# lt1236LS8_reference_module.net
KiCad netlist of a schematic drawn in EAGLE
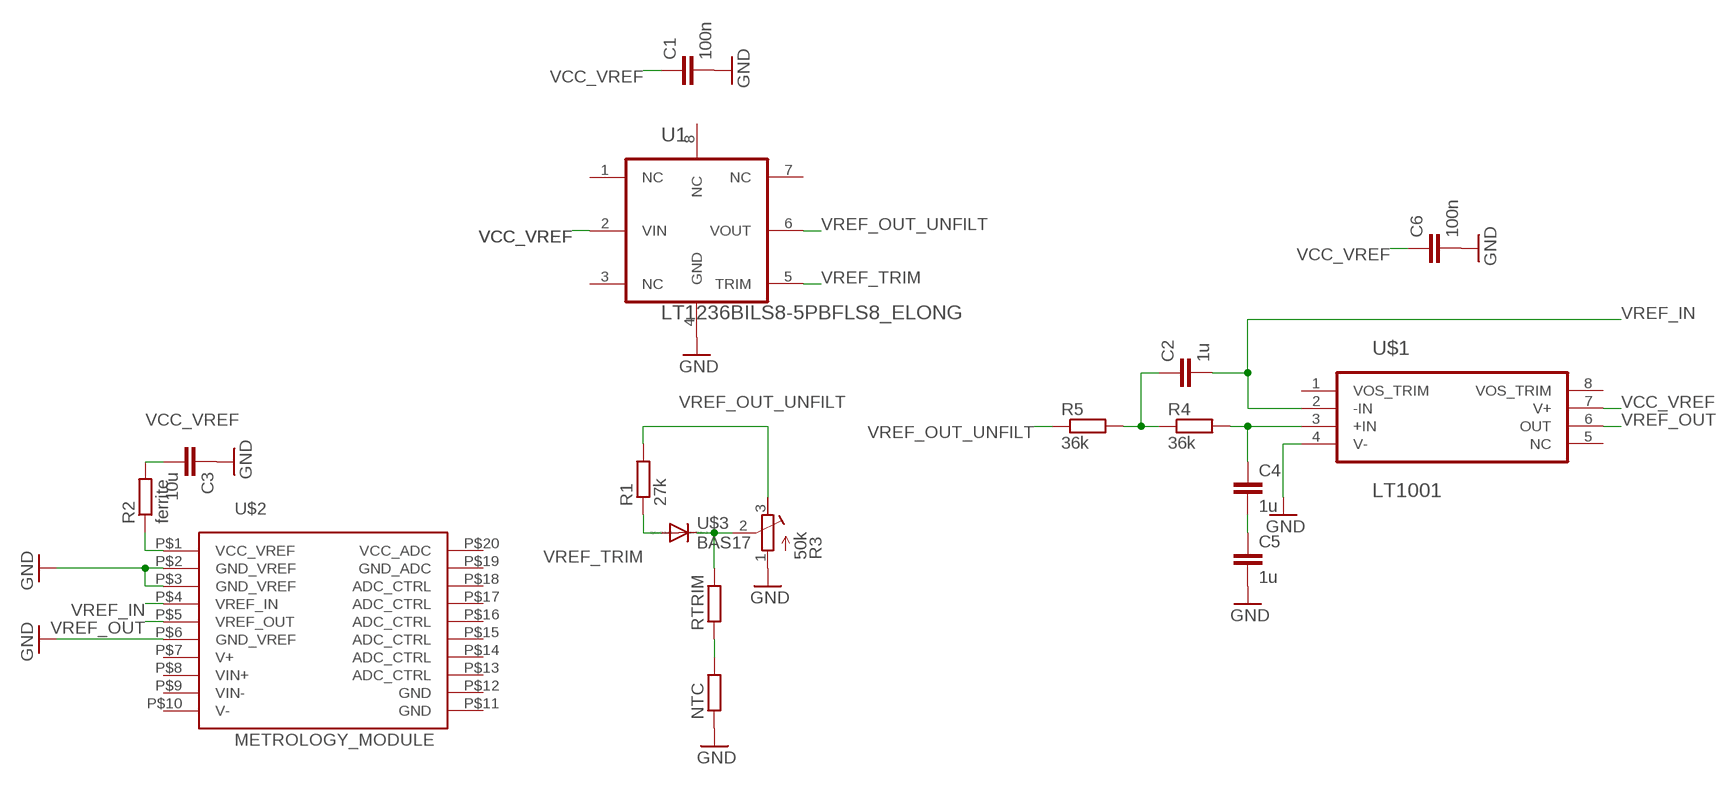
[diagram p0: schematic, sheet 1]

(export (version "E")
  (design (tool "Eeschema 10.0.6"))
  (components
    (comp (ref "C1")
      (value "100n")
      (footprint "eagle-import:C0603")
      (libsource (lib "eagle-import") (part "C-EUC0603"))
    )
    (comp (ref "C2")
      (value "1u")
      (footprint "eagle-import:C025-060X050")
      (libsource (lib "eagle-import") (part "C-EU025-060X050"))
    )
    (comp (ref "C3")
      (value "10u")
      (footprint "eagle-import:C0805")
      (libsource (lib "eagle-import") (part "C-EUC0805"))
    )
    (comp (ref "C4")
      (value "1u")
      (footprint "eagle-import:C025-060X050")
      (libsource (lib "eagle-import") (part "C-EU025-060X050"))
    )
    (comp (ref "C5")
      (value "1u")
      (footprint "eagle-import:C025-060X050")
      (libsource (lib "eagle-import") (part "C-EU025-060X050"))
    )
    (comp (ref "C6")
      (value "100n")
      (footprint "eagle-import:C0603")
      (libsource (lib "eagle-import") (part "C-EUC0603"))
    )
    (comp (ref "NTC")
      (value "R-EU_R0805")
      (footprint "eagle-import:R0805")
      (libsource (lib "eagle-import") (part "R-EU_R0805"))
    )
    (comp (ref "R1")
      (value "27k")
      (footprint "eagle-import:R0805")
      (libsource (lib "eagle-import") (part "R-EU_R0805"))
    )
    (comp (ref "R2")
      (value "ferrite")
      (footprint "eagle-import:R0805")
      (libsource (lib "eagle-import") (part "R-EU_R0805"))
    )
    (comp (ref "R3")
      (value "50k")
      (footprint "eagle-import:RTRIM3224W")
      (libsource (lib "eagle-import") (part "R-TRIMM3224W"))
    )
    (comp (ref "R4")
      (value "36k")
      (footprint "eagle-import:R0805")
      (libsource (lib "eagle-import") (part "R-EU_R0805"))
    )
    (comp (ref "R5")
      (value "36k")
      (footprint "eagle-import:R0805")
      (libsource (lib "eagle-import") (part "R-EU_R0805"))
    )
    (comp (ref "RTRIM")
      (value "R-EU_R0805")
      (footprint "eagle-import:R0805")
      (libsource (lib "eagle-import") (part "R-EU_R0805"))
    )
    (comp (ref "U$1")
      (value "LT1001")
      (footprint "eagle-import:N8-PDIP8")
      (libsource (lib "eagle-import") (part "LT1001"))
    )
    (comp (ref "U$2")
      (value "METROLOGY_MODULE")
      (footprint "eagle-import:METROLOGY_MODULE")
      (libsource (lib "eagle-import") (part "METROLOGY_MODULE"))
    )
    (comp (ref "U$3")
      (value "BAS17")
      (footprint "eagle-import:SOT23_HAND")
      (libsource (lib "eagle-import") (part "BAS17"))
    )
    (comp (ref "U1")
      (value "LT1236BILS8-5PBFLS8_ELONG")
      (footprint "eagle-import:LS8_ELONG")
      (libsource (lib "eagle-import") (part "LT1236BILS8-5PBFLS8_ELONG"))
    )
  )
  (nets
    (net (code "1") (name "/VCC_VREF") (class "Default")
      (node (ref "C1") (pin "1") (pinfunction "1_1") (pintype "passive"))
      (node (ref "C3") (pin "2") (pinfunction "2_2") (pintype "passive"))
      (node (ref "C6") (pin "1") (pinfunction "1_1") (pintype "passive"))
      (node (ref "R2") (pin "2") (pinfunction "2_2") (pintype "passive"))
      (node (ref "U$1") (pin "7") (pinfunction "V+_7") (pintype "bidirectional"))
      (node (ref "U1") (pin "2") (pinfunction "VIN_2") (pintype "input"))
    )
    (net (code "2") (name "/VREF_IN") (class "Default")
      (node (ref "C2") (pin "2") (pinfunction "2_2") (pintype "passive"))
      (node (ref "U$1") (pin "2") (pinfunction "-IN_2") (pintype "bidirectional"))
      (node (ref "U$2") (pin "P$4") (pinfunction "VREF_IN_P$4") (pintype "bidirectional"))
    )
    (net (code "3") (name "/VREF_OUT") (class "Default")
      (node (ref "U$1") (pin "6") (pinfunction "OUT_6") (pintype "bidirectional"))
      (node (ref "U$2") (pin "P$5") (pinfunction "VREF_OUT_P$5") (pintype "bidirectional"))
    )
    (net (code "4") (name "/VREF_OUT_UNFILT") (class "Default")
      (node (ref "R1") (pin "2") (pinfunction "2_2") (pintype "passive"))
      (node (ref "R3") (pin "3") (pinfunction "A_3") (pintype "passive"))
      (node (ref "R5") (pin "1") (pinfunction "1_1") (pintype "passive"))
      (node (ref "U1") (pin "6") (pinfunction "VOUT_6") (pintype "output"))
    )
    (net (code "5") (name "/VREF_TRIM") (class "Default")
      (node (ref "R1") (pin "1") (pinfunction "1_1") (pintype "passive"))
      (node (ref "U$3") (pin "1") (pinfunction "A_1") (pintype "passive"))
      (node (ref "U1") (pin "5") (pinfunction "TRIM_5") (pintype "input"))
    )
    (net (code "6") (name "GND") (class "Default")
      (node (ref "C1") (pin "2") (pinfunction "2_2") (pintype "passive"))
      (node (ref "C3") (pin "1") (pinfunction "1_1") (pintype "passive"))
      (node (ref "C5") (pin "2") (pinfunction "2_2") (pintype "passive"))
      (node (ref "C6") (pin "2") (pinfunction "2_2") (pintype "passive"))
      (node (ref "NTC") (pin "1") (pinfunction "1_1") (pintype "passive"))
      (node (ref "R3") (pin "1") (pinfunction "E_1") (pintype "passive"))
      (node (ref "U$1") (pin "4") (pinfunction "V-_4") (pintype "bidirectional"))
      (node (ref "U$2") (pin "P$2") (pinfunction "GND_VREF_P$2") (pintype "bidirectional"))
      (node (ref "U$2") (pin "P$3") (pinfunction "GND_VREF_P$3") (pintype "bidirectional"))
      (node (ref "U$2") (pin "P$6") (pinfunction "GND_VREF_P$6") (pintype "bidirectional"))
      (node (ref "U1") (pin "4") (pinfunction "GND_4") (pintype "passive"))
    )
    (net (code "7") (name "Net-(C2-Pad1)") (class "Default")
      (node (ref "C2") (pin "1") (pinfunction "1_1") (pintype "passive"))
      (node (ref "R4") (pin "1") (pinfunction "1_1") (pintype "passive"))
      (node (ref "R5") (pin "2") (pinfunction "2_2") (pintype "passive"))
    )
    (net (code "8") (name "Net-(C4-Pad2)") (class "Default")
      (node (ref "C4") (pin "2") (pinfunction "2_2") (pintype "passive"))
      (node (ref "C5") (pin "1") (pinfunction "1_1") (pintype "passive"))
    )
    (net (code "9") (name "Net-(NTC-Pad2)") (class "Default")
      (node (ref "NTC") (pin "2") (pinfunction "2_2") (pintype "passive"))
      (node (ref "RTRIM") (pin "1") (pinfunction "1_1") (pintype "passive"))
    )
    (net (code "10") (name "Net-(R3-S)") (class "Default")
      (node (ref "R3") (pin "2") (pinfunction "S_2") (pintype "passive"))
      (node (ref "RTRIM") (pin "2") (pinfunction "2_2") (pintype "passive"))
      (node (ref "U$3") (pin "3") (pinfunction "C_3") (pintype "passive"))
    )
    (net (code "11") (name "Net-(U$1-+IN)") (class "Default")
      (node (ref "C4") (pin "1") (pinfunction "1_1") (pintype "passive"))
      (node (ref "R4") (pin "2") (pinfunction "2_2") (pintype "passive"))
      (node (ref "U$1") (pin "3") (pinfunction "+IN_3") (pintype "bidirectional"))
    )
    (net (code "12") (name "Net-(U$2-VCC_VREF)") (class "Default")
      (node (ref "R2") (pin "1") (pinfunction "1_1") (pintype "passive"))
      (node (ref "U$2") (pin "P$1") (pinfunction "VCC_VREF_P$1") (pintype "bidirectional"))
    )
    (net (code "13") (name "unconnected-(U$1-NC-Pad5)") (class "Default")
      (node (ref "U$1") (pin "5") (pinfunction "NC_5") (pintype "bidirectional"))
    )
    (net (code "14") (name "unconnected-(U$1-VOS_TRIM-Pad1)") (class "Default")
      (node (ref "U$1") (pin "1") (pinfunction "VOS_TRIM_1") (pintype "bidirectional"))
    )
    (net (code "15") (name "unconnected-(U$1-VOS_TRIM-Pad8)") (class "Default")
      (node (ref "U$1") (pin "8") (pinfunction "VOS_TRIM_8") (pintype "bidirectional"))
    )
    (net (code "16") (name "unconnected-(U$2-ADC_CTRL-PadP$13)") (class "Default")
      (node (ref "U$2") (pin "P$13") (pinfunction "ADC_CTRL_P$13") (pintype "bidirectional"))
    )
    (net (code "17") (name "unconnected-(U$2-ADC_CTRL-PadP$14)") (class "Default")
      (node (ref "U$2") (pin "P$14") (pinfunction "ADC_CTRL_P$14") (pintype "bidirectional"))
    )
    (net (code "18") (name "unconnected-(U$2-ADC_CTRL-PadP$15)") (class "Default")
      (node (ref "U$2") (pin "P$15") (pinfunction "ADC_CTRL_P$15") (pintype "bidirectional"))
    )
    (net (code "19") (name "unconnected-(U$2-ADC_CTRL-PadP$16)") (class "Default")
      (node (ref "U$2") (pin "P$16") (pinfunction "ADC_CTRL_P$16") (pintype "bidirectional"))
    )
    (net (code "20") (name "unconnected-(U$2-ADC_CTRL-PadP$17)") (class "Default")
      (node (ref "U$2") (pin "P$17") (pinfunction "ADC_CTRL_P$17") (pintype "bidirectional"))
    )
    (net (code "21") (name "unconnected-(U$2-ADC_CTRL-PadP$18)") (class "Default")
      (node (ref "U$2") (pin "P$18") (pinfunction "ADC_CTRL_P$18") (pintype "bidirectional"))
    )
    (net (code "22") (name "unconnected-(U$2-GND-PadP$11)") (class "Default")
      (node (ref "U$2") (pin "P$11") (pinfunction "GND_P$11") (pintype "bidirectional"))
    )
    (net (code "23") (name "unconnected-(U$2-GND-PadP$12)") (class "Default")
      (node (ref "U$2") (pin "P$12") (pinfunction "GND_P$12") (pintype "bidirectional"))
    )
    (net (code "24") (name "unconnected-(U$2-GND_ADC-PadP$19)") (class "Default")
      (node (ref "U$2") (pin "P$19") (pinfunction "GND_ADC_P$19") (pintype "bidirectional"))
    )
    (net (code "25") (name "unconnected-(U$2-V+-PadP$7)") (class "Default")
      (node (ref "U$2") (pin "P$7") (pinfunction "V+_P$7") (pintype "bidirectional"))
    )
    (net (code "26") (name "unconnected-(U$2-V--PadP$10)") (class "Default")
      (node (ref "U$2") (pin "P$10") (pinfunction "V-_P$10") (pintype "bidirectional"))
    )
    (net (code "27") (name "unconnected-(U$2-VCC_ADC-PadP$20)") (class "Default")
      (node (ref "U$2") (pin "P$20") (pinfunction "VCC_ADC_P$20") (pintype "bidirectional"))
    )
    (net (code "28") (name "unconnected-(U$2-VIN+-PadP$8)") (class "Default")
      (node (ref "U$2") (pin "P$8") (pinfunction "VIN+_P$8") (pintype "bidirectional"))
    )
    (net (code "29") (name "unconnected-(U$2-VIN--PadP$9)") (class "Default")
      (node (ref "U$2") (pin "P$9") (pinfunction "VIN-_P$9") (pintype "bidirectional"))
    )
    (net (code "30") (name "unconnected-(U1-NC-Pad1)") (class "Default")
      (node (ref "U1") (pin "1") (pinfunction "NC_1") (pintype "no_connect"))
    )
    (net (code "31") (name "unconnected-(U1-NC-Pad3)") (class "Default")
      (node (ref "U1") (pin "3") (pinfunction "NC_3") (pintype "no_connect"))
    )
    (net (code "32") (name "unconnected-(U1-NC-Pad7)") (class "Default")
      (node (ref "U1") (pin "7") (pinfunction "NC_7") (pintype "no_connect"))
    )
    (net (code "33") (name "unconnected-(U1-NC-Pad8)") (class "Default")
      (node (ref "U1") (pin "8") (pinfunction "NC_8") (pintype "no_connect"))
    )
  )
)
